# 4P-18650-Mod-PCB.net
KiCad netlist of a schematic drawn in EAGLE
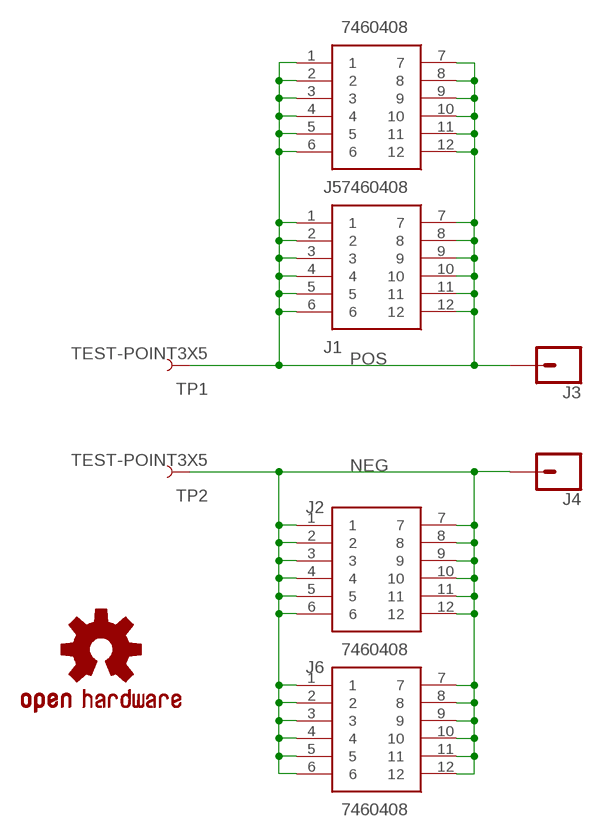
[diagram p0: schematic, sheet 1]

(export (version "E")
  (design (tool "Eeschema 10.0.6"))
  (components
    (comp (ref "J1")
      (value "7460408")
      (footprint "eagle-import:7460408")
      (fields (field (name "MOUSER_PART_NUMBER") "710-7460408"))
      (libsource (lib "eagle-import") (part "7460408"))
    )
    (comp (ref "J2")
      (value "7460408")
      (footprint "eagle-import:7460408")
      (fields (field (name "MOUSER_PART_NUMBER") "710-7460408"))
      (libsource (lib "eagle-import") (part "7460408"))
    )
    (comp (ref "J3")
      (value "CONN_01")
      (footprint "eagle-import:1X01")
      (libsource (lib "eagle-import") (part "CONN_01"))
    )
    (comp (ref "J4")
      (value "CONN_01")
      (footprint "eagle-import:1X01")
      (libsource (lib "eagle-import") (part "CONN_01"))
    )
    (comp (ref "J5")
      (value "7460408")
      (footprint "eagle-import:7460408")
      (fields (field (name "MOUSER_PART_NUMBER") "710-7460408"))
      (libsource (lib "eagle-import") (part "7460408"))
    )
    (comp (ref "J6")
      (value "7460408")
      (footprint "eagle-import:7460408")
      (fields (field (name "MOUSER_PART_NUMBER") "710-7460408"))
      (libsource (lib "eagle-import") (part "7460408"))
    )
    (comp (ref "LOGO1")
      (value "OSHW-LOGOL")
      (footprint "eagle-import:OSHW-LOGO-L")
      (libsource (lib "eagle-import") (part "OSHW-LOGOL"))
    )
    (comp (ref "TP1")
      (value "TEST-POINT3X5")
      (footprint "eagle-import:PAD.03X.05")
      (libsource (lib "eagle-import") (part "TEST-POINT3X5"))
    )
    (comp (ref "TP2")
      (value "TEST-POINT3X5")
      (footprint "eagle-import:PAD.03X.05")
      (libsource (lib "eagle-import") (part "TEST-POINT3X5"))
    )
  )
  (nets
    (net (code "1") (name "/NEG") (class "Default")
      (node (ref "J2") (pin "1") (pinfunction "1_1") (pintype "bidirectional"))
      (node (ref "J2") (pin "10") (pinfunction "10_10") (pintype "bidirectional"))
      (node (ref "J2") (pin "11") (pinfunction "11_11") (pintype "bidirectional"))
      (node (ref "J2") (pin "12") (pinfunction "12_12") (pintype "bidirectional"))
      (node (ref "J2") (pin "2") (pinfunction "2_2") (pintype "bidirectional"))
      (node (ref "J2") (pin "3") (pinfunction "3_3") (pintype "bidirectional"))
      (node (ref "J2") (pin "4") (pinfunction "4_4") (pintype "bidirectional"))
      (node (ref "J2") (pin "5") (pinfunction "5_5") (pintype "bidirectional"))
      (node (ref "J2") (pin "6") (pinfunction "6_6") (pintype "bidirectional"))
      (node (ref "J2") (pin "7") (pinfunction "7_7") (pintype "bidirectional"))
      (node (ref "J2") (pin "8") (pinfunction "8_8") (pintype "bidirectional"))
      (node (ref "J2") (pin "9") (pinfunction "9_9") (pintype "bidirectional"))
      (node (ref "J4") (pin "1") (pinfunction "1_1") (pintype "passive"))
      (node (ref "J6") (pin "1") (pinfunction "1_1") (pintype "bidirectional"))
      (node (ref "J6") (pin "10") (pinfunction "10_10") (pintype "bidirectional"))
      (node (ref "J6") (pin "11") (pinfunction "11_11") (pintype "bidirectional"))
      (node (ref "J6") (pin "12") (pinfunction "12_12") (pintype "bidirectional"))
      (node (ref "J6") (pin "2") (pinfunction "2_2") (pintype "bidirectional"))
      (node (ref "J6") (pin "3") (pinfunction "3_3") (pintype "bidirectional"))
      (node (ref "J6") (pin "4") (pinfunction "4_4") (pintype "bidirectional"))
      (node (ref "J6") (pin "5") (pinfunction "5_5") (pintype "bidirectional"))
      (node (ref "J6") (pin "6") (pinfunction "6_6") (pintype "bidirectional"))
      (node (ref "J6") (pin "7") (pinfunction "7_7") (pintype "bidirectional"))
      (node (ref "J6") (pin "8") (pinfunction "8_8") (pintype "bidirectional"))
      (node (ref "J6") (pin "9") (pinfunction "9_9") (pintype "bidirectional"))
      (node (ref "TP2") (pin "P$1") (pinfunction "1_P$1") (pintype "bidirectional"))
    )
    (net (code "2") (name "/POS") (class "Default")
      (node (ref "J1") (pin "1") (pinfunction "1_1") (pintype "bidirectional"))
      (node (ref "J1") (pin "10") (pinfunction "10_10") (pintype "bidirectional"))
      (node (ref "J1") (pin "11") (pinfunction "11_11") (pintype "bidirectional"))
      (node (ref "J1") (pin "12") (pinfunction "12_12") (pintype "bidirectional"))
      (node (ref "J1") (pin "2") (pinfunction "2_2") (pintype "bidirectional"))
      (node (ref "J1") (pin "3") (pinfunction "3_3") (pintype "bidirectional"))
      (node (ref "J1") (pin "4") (pinfunction "4_4") (pintype "bidirectional"))
      (node (ref "J1") (pin "5") (pinfunction "5_5") (pintype "bidirectional"))
      (node (ref "J1") (pin "6") (pinfunction "6_6") (pintype "bidirectional"))
      (node (ref "J1") (pin "7") (pinfunction "7_7") (pintype "bidirectional"))
      (node (ref "J1") (pin "8") (pinfunction "8_8") (pintype "bidirectional"))
      (node (ref "J1") (pin "9") (pinfunction "9_9") (pintype "bidirectional"))
      (node (ref "J3") (pin "1") (pinfunction "1_1") (pintype "passive"))
      (node (ref "J5") (pin "1") (pinfunction "1_1") (pintype "bidirectional"))
      (node (ref "J5") (pin "10") (pinfunction "10_10") (pintype "bidirectional"))
      (node (ref "J5") (pin "11") (pinfunction "11_11") (pintype "bidirectional"))
      (node (ref "J5") (pin "12") (pinfunction "12_12") (pintype "bidirectional"))
      (node (ref "J5") (pin "2") (pinfunction "2_2") (pintype "bidirectional"))
      (node (ref "J5") (pin "3") (pinfunction "3_3") (pintype "bidirectional"))
      (node (ref "J5") (pin "4") (pinfunction "4_4") (pintype "bidirectional"))
      (node (ref "J5") (pin "5") (pinfunction "5_5") (pintype "bidirectional"))
      (node (ref "J5") (pin "6") (pinfunction "6_6") (pintype "bidirectional"))
      (node (ref "J5") (pin "7") (pinfunction "7_7") (pintype "bidirectional"))
      (node (ref "J5") (pin "8") (pinfunction "8_8") (pintype "bidirectional"))
      (node (ref "J5") (pin "9") (pinfunction "9_9") (pintype "bidirectional"))
      (node (ref "TP1") (pin "P$1") (pinfunction "1_P$1") (pintype "bidirectional"))
    )
  )
)
